# tm7_matrix.net
KiCad netlist of a schematic drawn in EAGLE
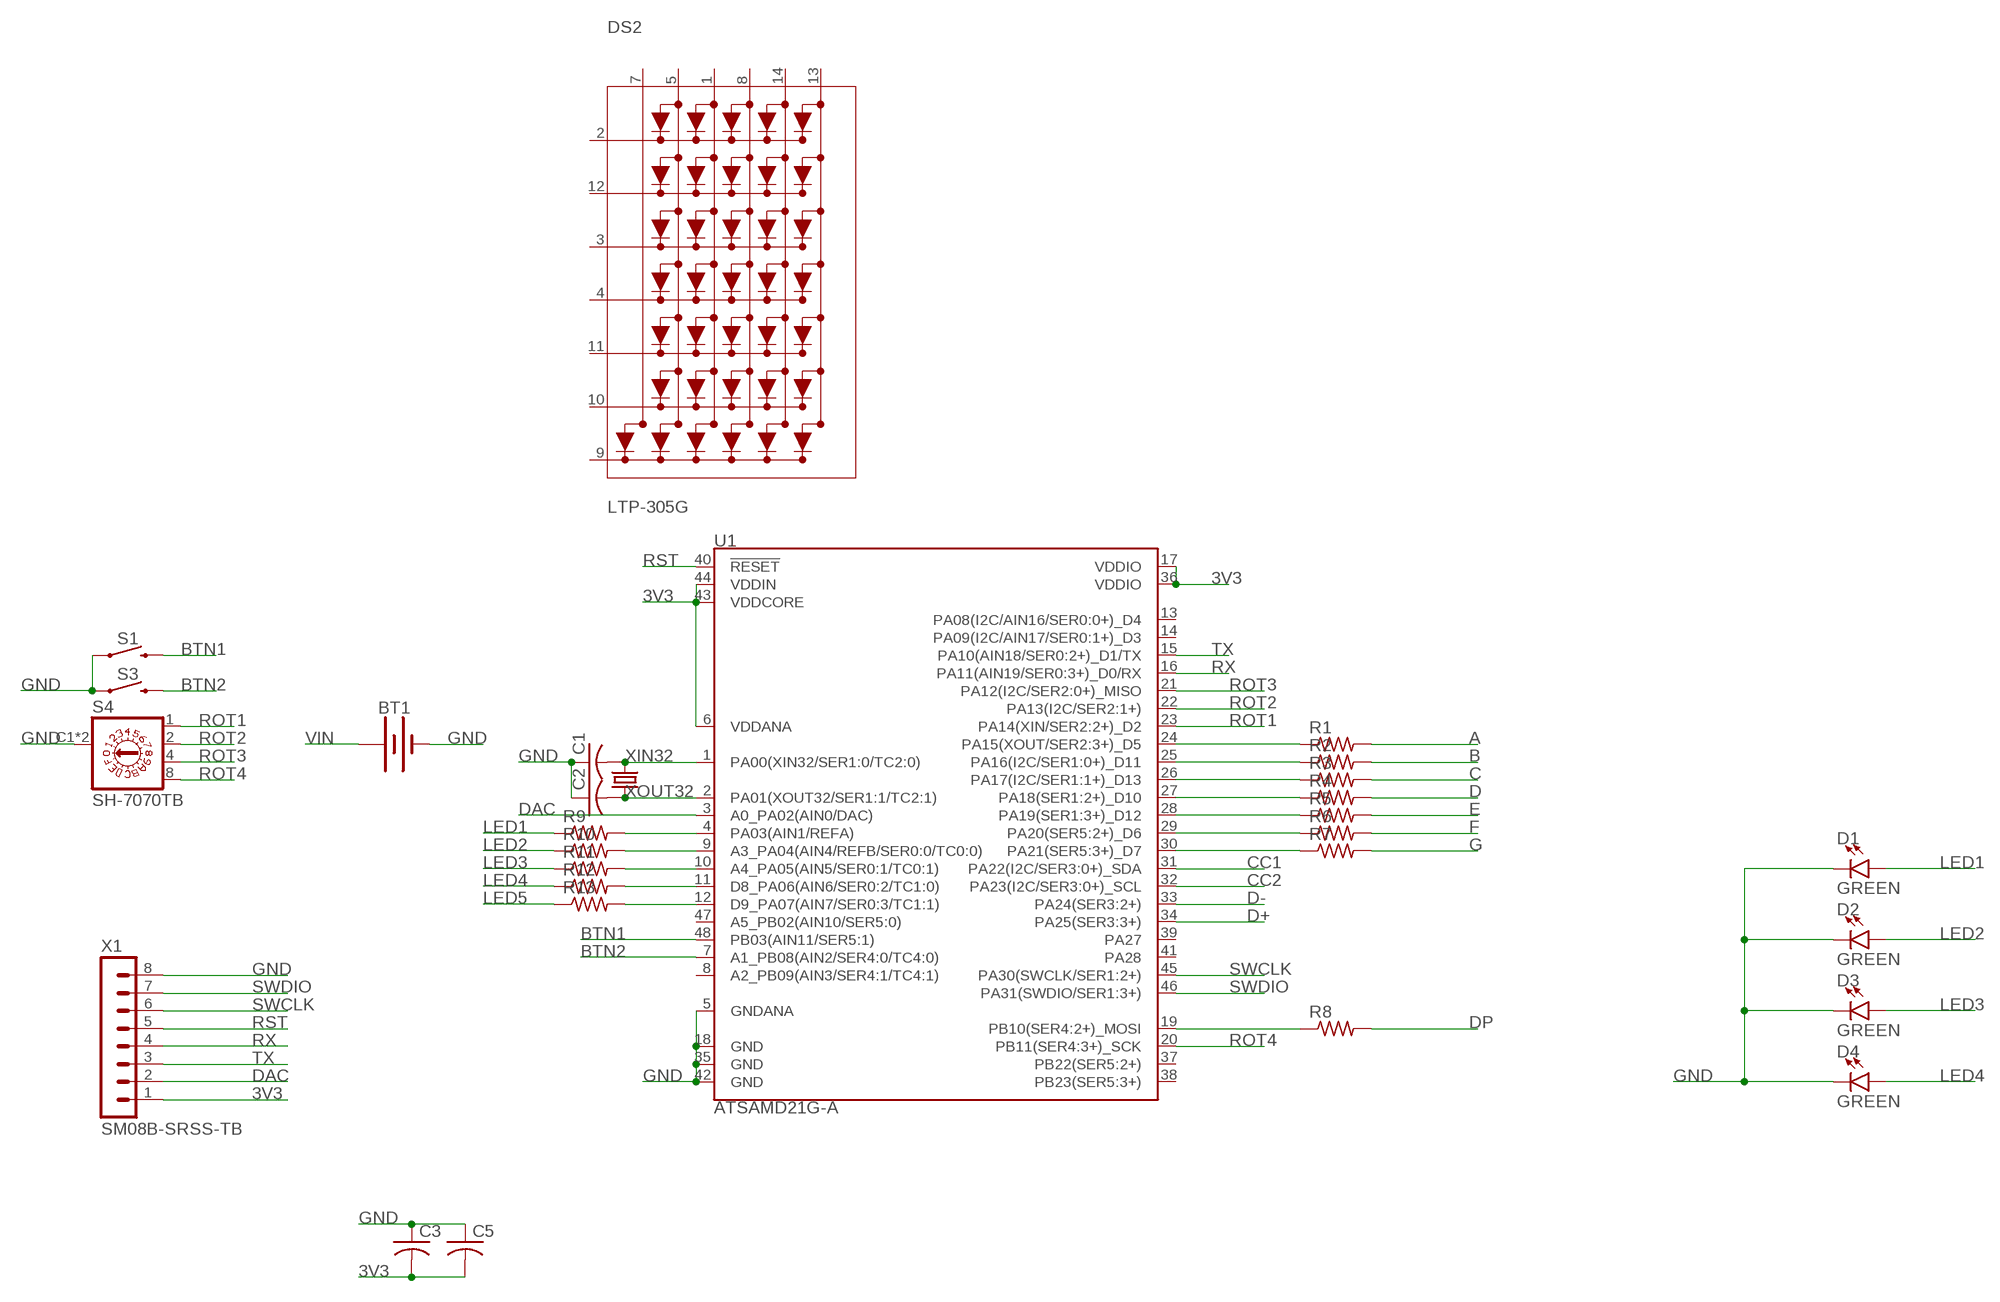
[diagram p0: schematic, sheet 1]

(export (version "E")
  (design (tool "Eeschema 10.0.6"))
  (components
    (comp (ref "BT1")
      (value "BATTERY-20MM_SMD_4LEGS_OVERPASTE_INNER")
      (footprint "eagle-import:BATTCON_20MM_4LEGS_OVERPASTE_INNER")
      (libsource (lib "eagle-import") (part "BATTERY-20MM_SMD_4LEGS_OVERPASTE_INNER"))
    )
    (comp (ref "C1")
      (value "C-USC0603")
      (footprint "eagle-import:C0603")
      (libsource (lib "eagle-import") (part "C-USC0603"))
    )
    (comp (ref "C2")
      (value "C-USC0603")
      (footprint "eagle-import:C0603")
      (libsource (lib "eagle-import") (part "C-USC0603"))
    )
    (comp (ref "C3")
      (value "C-USC0603")
      (footprint "eagle-import:C0603")
      (libsource (lib "eagle-import") (part "C-USC0603"))
    )
    (comp (ref "C5")
      (value "C-USC0603")
      (footprint "eagle-import:C0603")
      (libsource (lib "eagle-import") (part "C-USC0603"))
    )
    (comp (ref "D1")
      (value "GREEN")
      (footprint "eagle-import:LED-1206")
      (libsource (lib "eagle-import") (part "LED-GREEN1206"))
    )
    (comp (ref "D2")
      (value "GREEN")
      (footprint "eagle-import:LED-1206")
      (libsource (lib "eagle-import") (part "LED-GREEN1206"))
    )
    (comp (ref "D3")
      (value "GREEN")
      (footprint "eagle-import:LED-1206")
      (libsource (lib "eagle-import") (part "LED-GREEN1206"))
    )
    (comp (ref "D4")
      (value "GREEN")
      (footprint "eagle-import:LED-1206")
      (libsource (lib "eagle-import") (part "LED-GREEN1206"))
    )
    (comp (ref "DS2")
      (value "LTP-305G")
      (footprint "eagle-import:DIP762W50P254L1875H400Q13")
      (fields (field (name "MF") "Lite-On Inc."))
      (libsource (lib "eagle-import") (part "LTP-305G"))
    )
    (comp (ref "R1")
      (value "R-US_R0603")
      (footprint "eagle-import:R0603")
      (libsource (lib "eagle-import") (part "R-US_R0603"))
    )
    (comp (ref "R2")
      (value "R-US_R0603")
      (footprint "eagle-import:R0603")
      (libsource (lib "eagle-import") (part "R-US_R0603"))
    )
    (comp (ref "R3")
      (value "R-US_R0603")
      (footprint "eagle-import:R0603")
      (libsource (lib "eagle-import") (part "R-US_R0603"))
    )
    (comp (ref "R4")
      (value "R-US_R0603")
      (footprint "eagle-import:R0603")
      (libsource (lib "eagle-import") (part "R-US_R0603"))
    )
    (comp (ref "R5")
      (value "R-US_R0603")
      (footprint "eagle-import:R0603")
      (libsource (lib "eagle-import") (part "R-US_R0603"))
    )
    (comp (ref "R6")
      (value "R-US_R0603")
      (footprint "eagle-import:R0603")
      (libsource (lib "eagle-import") (part "R-US_R0603"))
    )
    (comp (ref "R7")
      (value "R-US_R0603")
      (footprint "eagle-import:R0603")
      (libsource (lib "eagle-import") (part "R-US_R0603"))
    )
    (comp (ref "R8")
      (value "R-US_R0603")
      (footprint "eagle-import:R0603")
      (libsource (lib "eagle-import") (part "R-US_R0603"))
    )
    (comp (ref "R9")
      (value "R-US_R0603")
      (footprint "eagle-import:R0603")
      (libsource (lib "eagle-import") (part "R-US_R0603"))
    )
    (comp (ref "R10")
      (value "R-US_R0603")
      (footprint "eagle-import:R0603")
      (libsource (lib "eagle-import") (part "R-US_R0603"))
    )
    (comp (ref "R11")
      (value "R-US_R0603")
      (footprint "eagle-import:R0603")
      (libsource (lib "eagle-import") (part "R-US_R0603"))
    )
    (comp (ref "R12")
      (value "R-US_R0603")
      (footprint "eagle-import:R0603")
      (libsource (lib "eagle-import") (part "R-US_R0603"))
    )
    (comp (ref "R13")
      (value "R-US_R0603")
      (footprint "eagle-import:R0603")
      (libsource (lib "eagle-import") (part "R-US_R0603"))
    )
    (comp (ref "S1")
      (value "MOMENTARY-SWITCH-SPST-SMD-6.2MM-TALL")
      (footprint "eagle-import:TACTILE_SWITCH_SMD_6.2MM_TALL")
      (libsource (lib "eagle-import") (part "MOMENTARY-SWITCH-SPST-SMD-6.2MM-TALL"))
    )
    (comp (ref "S3")
      (value "MOMENTARY-SWITCH-SPST-SMD-6.2MM-TALL")
      (footprint "eagle-import:TACTILE_SWITCH_SMD_6.2MM_TALL")
      (libsource (lib "eagle-import") (part "MOMENTARY-SWITCH-SPST-SMD-6.2MM-TALL"))
    )
    (comp (ref "S4")
      (value "SH-7070TB")
      (footprint "eagle-import:SH-7070B")
      (fields (field (name "MF") "Nidec Copal"))
      (libsource (lib "eagle-import") (part "SH-7070TB"))
    )
    (comp (ref "U1")
      (value "ATSAMD21G-A")
      (footprint "eagle-import:TQFP-48")
      (libsource (lib "eagle-import") (part "ATSAMD21G-A"))
    )
    (comp (ref "X1")
      (value "SM08B-SRSS-TB")
      (footprint "eagle-import:SM08B-SRSS-TB")
      (libsource (lib "eagle-import") (part "SM08B-SRSS-TB"))
    )
    (comp (ref "Y1")
      (value "32.768kHz")
      (footprint "eagle-import:CRYSTAL-SMD-3.2X1.5MM")
      (libsource (lib "eagle-import") (part "CRYSTAL-32.768KHZSMD-3.2X1.5"))
    )
  )
  (nets
    (net (code "1") (name "/3V3") (class "Default")
      (node (ref "C3") (pin "2") (pinfunction "2_2") (pintype "passive"))
      (node (ref "C5") (pin "2") (pinfunction "2_2") (pintype "passive"))
      (node (ref "U1") (pin "17") (pinfunction "VDDIO_17") (pintype "bidirectional"))
      (node (ref "U1") (pin "36") (pinfunction "VDDIO_36") (pintype "bidirectional"))
      (node (ref "U1") (pin "43") (pinfunction "VDDCORE_43") (pintype "bidirectional"))
      (node (ref "U1") (pin "44") (pinfunction "VDDIN_44") (pintype "bidirectional"))
      (node (ref "U1") (pin "6") (pinfunction "VDDANA_6") (pintype "bidirectional"))
      (node (ref "X1") (pin "1") (pinfunction "1_1") (pintype "passive"))
    )
    (net (code "2") (name "/A") (class "Default")
      (node (ref "R1") (pin "2") (pinfunction "2_2") (pintype "passive"))
    )
    (net (code "3") (name "/B") (class "Default")
      (node (ref "R2") (pin "2") (pinfunction "2_2") (pintype "passive"))
    )
    (net (code "4") (name "/BTN1") (class "Default")
      (node (ref "S1") (pin "B2") (pinfunction "2_B2") (pintype "passive"))
      (node (ref "U1") (pin "48") (pinfunction "PB03(AIN11/SER5:1)_48") (pintype "bidirectional"))
    )
    (net (code "5") (name "/BTN2") (class "Default")
      (node (ref "S3") (pin "B2") (pinfunction "2_B2") (pintype "passive"))
      (node (ref "U1") (pin "7") (pinfunction "A1_PB08(AIN2/SER4:0/TC4:0)_7") (pintype "bidirectional"))
    )
    (net (code "6") (name "/C") (class "Default")
      (node (ref "R3") (pin "2") (pinfunction "2_2") (pintype "passive"))
    )
    (net (code "7") (name "/CC1") (class "Default")
      (node (ref "U1") (pin "31") (pinfunction "PA22(I2C/SER3:0+)_SDA_31") (pintype "bidirectional"))
    )
    (net (code "8") (name "/CC2") (class "Default")
      (node (ref "U1") (pin "32") (pinfunction "PA23(I2C/SER3:0+)_SCL_32") (pintype "bidirectional"))
    )
    (net (code "9") (name "/D") (class "Default")
      (node (ref "R4") (pin "2") (pinfunction "2_2") (pintype "passive"))
    )
    (net (code "10") (name "/D+") (class "Default")
      (node (ref "U1") (pin "34") (pinfunction "PA25(SER3:3+)_34") (pintype "bidirectional"))
    )
    (net (code "11") (name "/D-") (class "Default")
      (node (ref "U1") (pin "33") (pinfunction "PA24(SER3:2+)_33") (pintype "bidirectional"))
    )
    (net (code "12") (name "/DAC") (class "Default")
      (node (ref "U1") (pin "3") (pinfunction "A0_PA02(AIN0/DAC)_3") (pintype "bidirectional"))
      (node (ref "X1") (pin "2") (pinfunction "2_2") (pintype "passive"))
    )
    (net (code "13") (name "/DP") (class "Default")
      (node (ref "R8") (pin "2") (pinfunction "2_2") (pintype "passive"))
    )
    (net (code "14") (name "/E") (class "Default")
      (node (ref "R5") (pin "2") (pinfunction "2_2") (pintype "passive"))
    )
    (net (code "15") (name "/F") (class "Default")
      (node (ref "R6") (pin "2") (pinfunction "2_2") (pintype "passive"))
    )
    (net (code "16") (name "/G") (class "Default")
      (node (ref "R7") (pin "2") (pinfunction "2_2") (pintype "passive"))
    )
    (net (code "17") (name "/GND") (class "Default")
      (node (ref "BT1") (pin "2") (pinfunction "-_2") (pintype "power_in"))
      (node (ref "C1") (pin "1") (pinfunction "1_1") (pintype "passive"))
      (node (ref "C2") (pin "1") (pinfunction "1_1") (pintype "passive"))
      (node (ref "C3") (pin "1") (pinfunction "1_1") (pintype "passive"))
      (node (ref "C5") (pin "1") (pinfunction "1_1") (pintype "passive"))
      (node (ref "D1") (pin "C") (pinfunction "C_C") (pintype "passive"))
      (node (ref "D2") (pin "C") (pinfunction "C_C") (pintype "passive"))
      (node (ref "D3") (pin "C") (pinfunction "C_C") (pintype "passive"))
      (node (ref "D4") (pin "C") (pinfunction "C_C") (pintype "passive"))
      (node (ref "S1") (pin "A2") (pinfunction "1_A2") (pintype "passive"))
      (node (ref "S3") (pin "A2") (pinfunction "1_A2") (pintype "passive"))
      (node (ref "S4") (pin "C1") (pinfunction "C_C1") (pintype "passive"))
      (node (ref "S4") (pin "C2") (pinfunction "C_C2") (pintype "passive"))
      (node (ref "U1") (pin "18") (pinfunction "GND_18") (pintype "bidirectional"))
      (node (ref "U1") (pin "35") (pinfunction "GND_35") (pintype "bidirectional"))
      (node (ref "U1") (pin "42") (pinfunction "GND_42") (pintype "bidirectional"))
      (node (ref "U1") (pin "5") (pinfunction "GNDANA_5") (pintype "bidirectional"))
      (node (ref "X1") (pin "8") (pinfunction "8_8") (pintype "passive"))
    )
    (net (code "18") (name "/LED1") (class "Default")
      (node (ref "D1") (pin "A") (pinfunction "A_A") (pintype "passive"))
      (node (ref "R9") (pin "1") (pinfunction "1_1") (pintype "passive"))
    )
    (net (code "19") (name "/LED2") (class "Default")
      (node (ref "D2") (pin "A") (pinfunction "A_A") (pintype "passive"))
      (node (ref "R10") (pin "1") (pinfunction "1_1") (pintype "passive"))
    )
    (net (code "20") (name "/LED3") (class "Default")
      (node (ref "D3") (pin "A") (pinfunction "A_A") (pintype "passive"))
      (node (ref "R11") (pin "1") (pinfunction "1_1") (pintype "passive"))
    )
    (net (code "21") (name "/LED4") (class "Default")
      (node (ref "D4") (pin "A") (pinfunction "A_A") (pintype "passive"))
      (node (ref "R12") (pin "1") (pinfunction "1_1") (pintype "passive"))
    )
    (net (code "22") (name "/LED5") (class "Default")
      (node (ref "R13") (pin "1") (pinfunction "1_1") (pintype "passive"))
    )
    (net (code "23") (name "/ROT1") (class "Default")
      (node (ref "S4") (pin "1") (pinfunction "1_1") (pintype "passive"))
      (node (ref "U1") (pin "23") (pinfunction "PA14(XIN/SER2:2+)_D2_23") (pintype "bidirectional"))
    )
    (net (code "24") (name "/ROT2") (class "Default")
      (node (ref "S4") (pin "2") (pinfunction "2_2") (pintype "passive"))
      (node (ref "U1") (pin "22") (pinfunction "PA13(I2C/SER2:1+)_22") (pintype "bidirectional"))
    )
    (net (code "25") (name "/ROT3") (class "Default")
      (node (ref "S4") (pin "4") (pinfunction "4_4") (pintype "passive"))
      (node (ref "U1") (pin "21") (pinfunction "PA12(I2C/SER2:0+)_MISO_21") (pintype "bidirectional"))
    )
    (net (code "26") (name "/ROT4") (class "Default")
      (node (ref "S4") (pin "8") (pinfunction "8_8") (pintype "passive"))
      (node (ref "U1") (pin "20") (pinfunction "PB11(SER4:3+)_SCK_20") (pintype "bidirectional"))
    )
    (net (code "27") (name "/RST") (class "Default")
      (node (ref "U1") (pin "40") (pinfunction "~{RESET}_40") (pintype "bidirectional"))
      (node (ref "X1") (pin "5") (pinfunction "5_5") (pintype "passive"))
    )
    (net (code "28") (name "/RX") (class "Default")
      (node (ref "U1") (pin "16") (pinfunction "PA11(AIN19/SER0:3+)_D0/RX_16") (pintype "bidirectional"))
      (node (ref "X1") (pin "4") (pinfunction "4_4") (pintype "passive"))
    )
    (net (code "29") (name "/SWCLK") (class "Default")
      (node (ref "U1") (pin "45") (pinfunction "PA30(SWCLK/SER1:2+)_45") (pintype "bidirectional"))
      (node (ref "X1") (pin "6") (pinfunction "6_6") (pintype "passive"))
    )
    (net (code "30") (name "/SWDIO") (class "Default")
      (node (ref "U1") (pin "46") (pinfunction "PA31(SWDIO/SER1:3+)_46") (pintype "bidirectional"))
      (node (ref "X1") (pin "7") (pinfunction "7_7") (pintype "passive"))
    )
    (net (code "31") (name "/TX") (class "Default")
      (node (ref "U1") (pin "15") (pinfunction "PA10(AIN18/SER0:2+)_D1/TX_15") (pintype "bidirectional"))
      (node (ref "X1") (pin "3") (pinfunction "3_3") (pintype "passive"))
    )
    (net (code "32") (name "/VIN") (class "Default")
      (node (ref "BT1") (pin "1") (pinfunction "+_1") (pintype "power_in"))
    )
    (net (code "33") (name "/XIN32") (class "Default")
      (node (ref "C1") (pin "2") (pinfunction "2_2") (pintype "passive"))
      (node (ref "U1") (pin "1") (pinfunction "PA00(XIN32/SER1:0/TC2:0)_1") (pintype "bidirectional"))
      (node (ref "Y1") (pin "P$2") (pinfunction "2_P$2") (pintype "passive"))
    )
    (net (code "34") (name "/XOUT32") (class "Default")
      (node (ref "C2") (pin "2") (pinfunction "2_2") (pintype "passive"))
      (node (ref "U1") (pin "2") (pinfunction "PA01(XOUT32/SER1:1/TC2:1)_2") (pintype "bidirectional"))
      (node (ref "Y1") (pin "P$1") (pinfunction "1_P$1") (pintype "passive"))
    )
    (net (code "35") (name "Net-(U1-A3_PA04(AIN4{slash}REFB{slash}SER0:0{slash}TC0:0))") (class "Default")
      (node (ref "R10") (pin "2") (pinfunction "2_2") (pintype "passive"))
      (node (ref "U1") (pin "9") (pinfunction "A3_PA04(AIN4/REFB/SER0:0/TC0:0)_9") (pintype "bidirectional"))
    )
    (net (code "36") (name "Net-(U1-A4_PA05(AIN5{slash}SER0:1{slash}TC0:1))") (class "Default")
      (node (ref "R11") (pin "2") (pinfunction "2_2") (pintype "passive"))
      (node (ref "U1") (pin "10") (pinfunction "A4_PA05(AIN5/SER0:1/TC0:1)_10") (pintype "bidirectional"))
    )
    (net (code "37") (name "Net-(U1-D8_PA06(AIN6{slash}SER0:2{slash}TC1:0))") (class "Default")
      (node (ref "R12") (pin "2") (pinfunction "2_2") (pintype "passive"))
      (node (ref "U1") (pin "11") (pinfunction "D8_PA06(AIN6/SER0:2/TC1:0)_11") (pintype "bidirectional"))
    )
    (net (code "38") (name "Net-(U1-D9_PA07(AIN7{slash}SER0:3{slash}TC1:1))") (class "Default")
      (node (ref "R13") (pin "2") (pinfunction "2_2") (pintype "passive"))
      (node (ref "U1") (pin "12") (pinfunction "D9_PA07(AIN7/SER0:3/TC1:1)_12") (pintype "bidirectional"))
    )
    (net (code "39") (name "Net-(U1-PA03(AIN1{slash}REFA))") (class "Default")
      (node (ref "R9") (pin "2") (pinfunction "2_2") (pintype "passive"))
      (node (ref "U1") (pin "4") (pinfunction "PA03(AIN1/REFA)_4") (pintype "bidirectional"))
    )
    (net (code "40") (name "Net-(U1-PA15(XOUT{slash}SER2:3+)_D5)") (class "Default")
      (node (ref "R1") (pin "1") (pinfunction "1_1") (pintype "passive"))
      (node (ref "U1") (pin "24") (pinfunction "PA15(XOUT/SER2:3+)_D5_24") (pintype "bidirectional"))
    )
    (net (code "41") (name "Net-(U1-PA16(I2C{slash}SER1:0+)_D11)") (class "Default")
      (node (ref "R2") (pin "1") (pinfunction "1_1") (pintype "passive"))
      (node (ref "U1") (pin "25") (pinfunction "PA16(I2C/SER1:0+)_D11_25") (pintype "bidirectional"))
    )
    (net (code "42") (name "Net-(U1-PA17(I2C{slash}SER1:1+)_D13)") (class "Default")
      (node (ref "R3") (pin "1") (pinfunction "1_1") (pintype "passive"))
      (node (ref "U1") (pin "26") (pinfunction "PA17(I2C/SER1:1+)_D13_26") (pintype "bidirectional"))
    )
    (net (code "43") (name "Net-(U1-PA18(SER1:2+)_D10)") (class "Default")
      (node (ref "R4") (pin "1") (pinfunction "1_1") (pintype "passive"))
      (node (ref "U1") (pin "27") (pinfunction "PA18(SER1:2+)_D10_27") (pintype "bidirectional"))
    )
    (net (code "44") (name "Net-(U1-PA19(SER1:3+)_D12)") (class "Default")
      (node (ref "R5") (pin "1") (pinfunction "1_1") (pintype "passive"))
      (node (ref "U1") (pin "28") (pinfunction "PA19(SER1:3+)_D12_28") (pintype "bidirectional"))
    )
    (net (code "45") (name "Net-(U1-PA20(SER5:2+)_D6)") (class "Default")
      (node (ref "R6") (pin "1") (pinfunction "1_1") (pintype "passive"))
      (node (ref "U1") (pin "29") (pinfunction "PA20(SER5:2+)_D6_29") (pintype "bidirectional"))
    )
    (net (code "46") (name "Net-(U1-PA21(SER5:3+)_D7)") (class "Default")
      (node (ref "R7") (pin "1") (pinfunction "1_1") (pintype "passive"))
      (node (ref "U1") (pin "30") (pinfunction "PA21(SER5:3+)_D7_30") (pintype "bidirectional"))
    )
    (net (code "47") (name "Net-(U1-PB10(SER4:2+)_MOSI)") (class "Default")
      (node (ref "R8") (pin "1") (pinfunction "1_1") (pintype "passive"))
      (node (ref "U1") (pin "19") (pinfunction "PB10(SER4:2+)_MOSI_19") (pintype "bidirectional"))
    )
    (net (code "48") (name "unconnected-(DS2-ANODE_COLUMN_1-Pad5)") (class "Default")
      (node (ref "DS2") (pin "5") (pinfunction "ANODE_COLUMN_1_5") (pintype "passive"))
    )
    (net (code "49") (name "unconnected-(DS2-ANODE_COLUMN_2-Pad1)") (class "Default")
      (node (ref "DS2") (pin "1") (pinfunction "ANODE_COLUMN_2_1") (pintype "passive"))
    )
    (net (code "50") (name "unconnected-(DS2-ANODE_COLUMN_3-Pad8)") (class "Default")
      (node (ref "DS2") (pin "8") (pinfunction "ANODE_COLUMN_3_8") (pintype "passive"))
    )
    (net (code "51") (name "unconnected-(DS2-ANODE_COLUMN_4-Pad14)") (class "Default")
      (node (ref "DS2") (pin "14") (pinfunction "ANODE_COLUMN_4_14") (pintype "passive"))
    )
    (net (code "52") (name "unconnected-(DS2-ANODE_COLUMN_5-Pad13)") (class "Default")
      (node (ref "DS2") (pin "13") (pinfunction "ANODE_COLUMN_5_13") (pintype "passive"))
    )
    (net (code "53") (name "unconnected-(DS2-ANODE_DECIMAL_POINT-Pad7)") (class "Default")
      (node (ref "DS2") (pin "7") (pinfunction "ANODE_DECIMAL_POINT_7") (pintype "passive"))
    )
    (net (code "54") (name "unconnected-(DS2-CATHODE_ROW_1-Pad2)") (class "Default")
      (node (ref "DS2") (pin "2") (pinfunction "CATHODE_ROW_1_2") (pintype "passive"))
    )
    (net (code "55") (name "unconnected-(DS2-CATHODE_ROW_2-Pad12)") (class "Default")
      (node (ref "DS2") (pin "12") (pinfunction "CATHODE_ROW_2_12") (pintype "passive"))
    )
    (net (code "56") (name "unconnected-(DS2-CATHODE_ROW_3-Pad3)") (class "Default")
      (node (ref "DS2") (pin "3") (pinfunction "CATHODE_ROW_3_3") (pintype "passive"))
    )
    (net (code "57") (name "unconnected-(DS2-CATHODE_ROW_4-Pad4)") (class "Default")
      (node (ref "DS2") (pin "4") (pinfunction "CATHODE_ROW_4_4") (pintype "passive"))
    )
    (net (code "58") (name "unconnected-(DS2-CATHODE_ROW_5-Pad11)") (class "Default")
      (node (ref "DS2") (pin "11") (pinfunction "CATHODE_ROW_5_11") (pintype "passive"))
    )
    (net (code "59") (name "unconnected-(DS2-CATHODE_ROW_6-Pad10)") (class "Default")
      (node (ref "DS2") (pin "10") (pinfunction "CATHODE_ROW_6_10") (pintype "passive"))
    )
    (net (code "60") (name "unconnected-(DS2-CATHODE_ROW_7-Pad9)") (class "Default")
      (node (ref "DS2") (pin "9") (pinfunction "CATHODE_ROW_7_9") (pintype "passive"))
    )
    (net (code "61") (name "unconnected-(U1-A2_PB09(AIN3{slash}SER4:1{slash}TC4:1)-Pad8)") (class "Default")
      (node (ref "U1") (pin "8") (pinfunction "A2_PB09(AIN3/SER4:1/TC4:1)_8") (pintype "bidirectional"))
    )
    (net (code "62") (name "unconnected-(U1-A5_PB02(AIN10{slash}SER5:0)-Pad47)") (class "Default")
      (node (ref "U1") (pin "47") (pinfunction "A5_PB02(AIN10/SER5:0)_47") (pintype "bidirectional"))
    )
    (net (code "63") (name "unconnected-(U1-PA08(I2C{slash}AIN16{slash}SER0:0+)_D4-Pad13)") (class "Default")
      (node (ref "U1") (pin "13") (pinfunction "PA08(I2C/AIN16/SER0:0+)_D4_13") (pintype "bidirectional"))
    )
    (net (code "64") (name "unconnected-(U1-PA09(I2C{slash}AIN17{slash}SER0:1+)_D3-Pad14)") (class "Default")
      (node (ref "U1") (pin "14") (pinfunction "PA09(I2C/AIN17/SER0:1+)_D3_14") (pintype "bidirectional"))
    )
    (net (code "65") (name "unconnected-(U1-PA27-Pad39)") (class "Default")
      (node (ref "U1") (pin "39") (pinfunction "PA27_39") (pintype "bidirectional"))
    )
    (net (code "66") (name "unconnected-(U1-PA28-Pad41)") (class "Default")
      (node (ref "U1") (pin "41") (pinfunction "PA28_41") (pintype "bidirectional"))
    )
    (net (code "67") (name "unconnected-(U1-PB22(SER5:2+)-Pad37)") (class "Default")
      (node (ref "U1") (pin "37") (pinfunction "PB22(SER5:2+)_37") (pintype "bidirectional"))
    )
    (net (code "68") (name "unconnected-(U1-PB23(SER5:3+)-Pad38)") (class "Default")
      (node (ref "U1") (pin "38") (pinfunction "PB23(SER5:3+)_38") (pintype "bidirectional"))
    )
  )
)
